# 07_RS485.net
KiCad netlist of a schematic drawn in Altium Designer
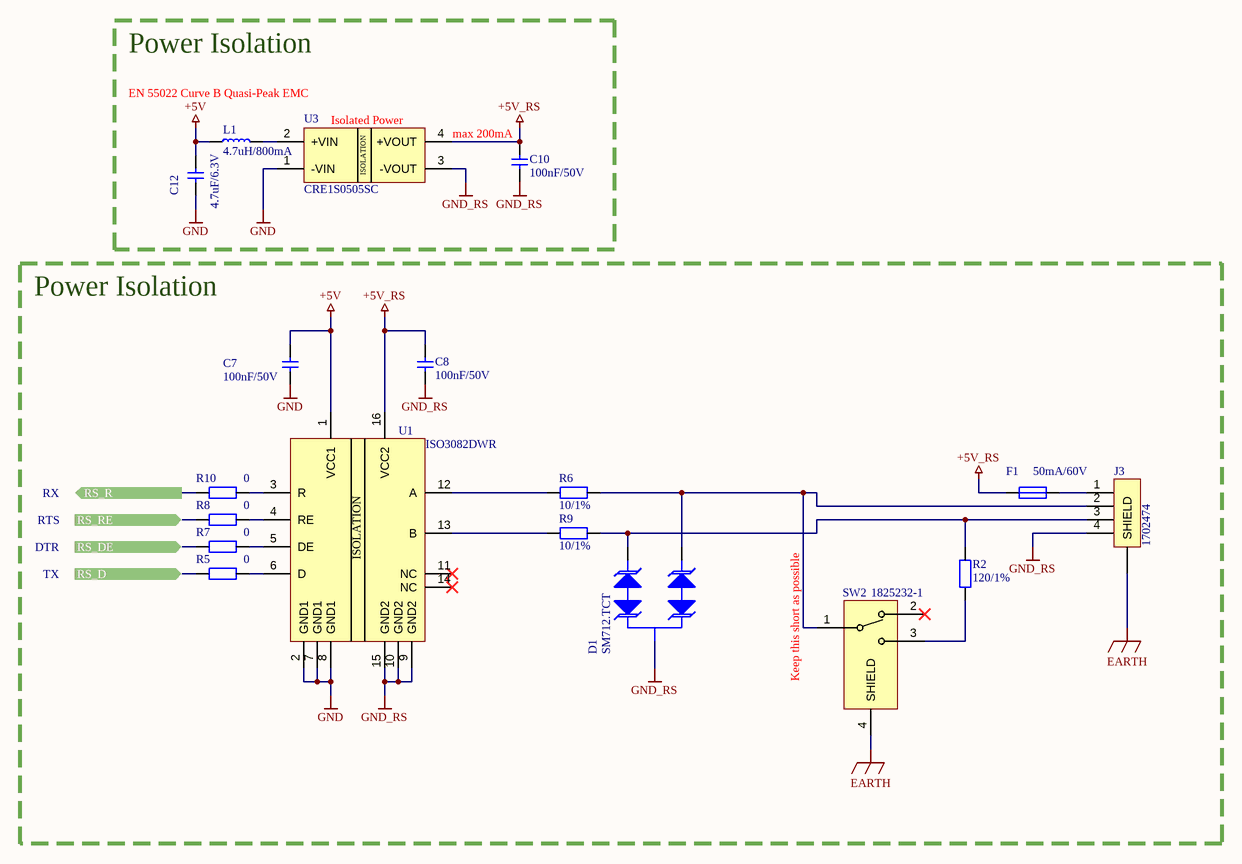
[diagram p0: 07 RS485.SchDoc]

(export (version "E")
  (design (tool "Eeschema 10.0.6"))
  (components
    (comp (ref "C7")
      (value "100nF/50V")
      (footprint "CAPC1005X06N")
      (description "0.1 µF ±10% 50V Ceramic Capacitor X7R 0402 (1005 Metric)")
      (fields
        (field (name "MANUFACTURER") "Murata Electronics")
        (field (name "MFR_PART_NUMBER") "GCM155R71H104KE02J")
      )
      (libsource (lib "altium_symbol") (part "GCM155R71H104KE02J"))
    )
    (comp (ref "C8")
      (value "100nF/50V")
      (footprint "CAPC1005X06N")
      (description "0.1 µF ±10% 50V Ceramic Capacitor X7R 0402 (1005 Metric)")
      (fields
        (field (name "MANUFACTURER") "Murata Electronics")
        (field (name "MFR_PART_NUMBER") "GCM155R71H104KE02J")
      )
      (libsource (lib "altium_symbol") (part "GCM155R71H104KE02J"))
    )
    (comp (ref "C10")
      (value "100nF/50V")
      (footprint "CAPC1005X06N")
      (description "0.1 µF ±10% 50V Ceramic Capacitor X7R 0402 (1005 Metric)")
      (fields
        (field (name "MANUFACTURER") "Murata Electronics")
        (field (name "MFR_PART_NUMBER") "GCM155R71H104KE02J")
      )
      (libsource (lib "altium_symbol") (part "GCM155R71H104KE02J"))
    )
    (comp (ref "C12")
      (value "4.7uF/6.3V")
      (footprint "CAPC1005X06N")
      (description "4.7 µF ±20% 6.3V Ceramic Capacitor X5R 0402 (1005 Metric)")
      (fields (field (name "MANUFACTURER") "Taiyo Yuden") (field (name "MFR_PART_NUMBER") "JMK105BBJ475MVHF"))
      (libsource (lib "altium_symbol") (part "JMK105BBJ475MVHF"))
    )
    (comp (ref "D1")
      (value "SM712.TCT")
      (footprint "SOT95P237X110-3N")
      (description "26V, 12V Clamp 17A (8/20µs) Ipp Tvs Diode Surface Mount SOT-23-3")
      (fields (field (name "MANUFACTURER") "Semtech Corporation"))
      (libsource (lib "altium_symbol") (part "SM712.TCT"))
    )
    (comp (ref "F1")
      (value "50mA/60V")
      (footprint "DIOC1005X04N")
      (description "Polymeric PTC Resettable Fuse 60V 50 mA Ih Surface Mount 1206 (3216 Metric), Concave")
      (fields (field (name "MANUFACTURER") "Bel Fuse Inc.") (field (name "MFR_PART_NUMBER") "0ZCJ0005FF2E"))
      (libsource (lib "altium_symbol") (part "0ZCJ0005FF2E"))
    )
    (comp (ref "J3")
      (value "1702474")
      (footprint "1702474")
      (description "4 Position Wire to Board Terminal Block Horizontal with Board 0.098\" (2.50mm) Surface Mount")
      (fields (field (name "MANUFACTURER") "Phoenix Contact"))
      (libsource (lib "altium_symbol") (part "1702474"))
    )
    (comp (ref "L1")
      (value "4.7uH/800mA")
      (footprint "INDP3225X23N")
      (description "4.7 µH Unshielded Wirewound Inductor 800 mA 190mOhm Max 1210 (3225 Metric)")
      (fields
        (field (name "MANUFACTURER") "Murata Power Solutions Inc.")
        (field (name "MFR_PART_NUMBER") "82472C")
      )
      (libsource (lib "altium_symbol") (part "82472C"))
    )
    (comp (ref "R2")
      (value "120/1%")
      (footprint "RESC1005X04N")
      (description "120 Ohms ±1% 0.1W, 1/10W Chip Resistor 0402 (1005 Metric) Automotive AEC-Q200 Thick Film")
      (fields
        (field (name "MANUFACTURER") "Panasonic Electronic Components")
        (field (name "MFR_PART_NUMBER") "ERJ-2RKF1200X")
      )
      (libsource (lib "altium_symbol") (part "ERJ-2RKF1200X"))
    )
    (comp (ref "R5")
      (value "0")
      (footprint "RESC1005X04N")
      (description "0 Ohms Jumper Chip Resistor 0402 (1005 Metric) Automotive AEC-Q200 Thick Film")
      (fields
        (field (name "MANUFACTURER") "Panasonic Electronic Components")
        (field (name "MFR_PART_NUMBER") "ERJ-2GE0R00X")
      )
      (libsource (lib "altium_symbol") (part "ERJ-2GE0R00X"))
    )
    (comp (ref "R6")
      (value "10/1%")
      (footprint "RESMELF3614N")
      (fields
        (field (name "MANUFACTURER") "Vishay Beyschlag/Draloric/BC Components")
        (field (name "MFR_PART_NUMBER") "SMM02040C1009FB300")
      )
      (libsource (lib "altium_symbol") (part "SMM02040C1009FB300"))
    )
    (comp (ref "R7")
      (value "0")
      (footprint "RESC1005X04N")
      (description "0 Ohms Jumper Chip Resistor 0402 (1005 Metric) Automotive AEC-Q200 Thick Film")
      (fields
        (field (name "MANUFACTURER") "Panasonic Electronic Components")
        (field (name "MFR_PART_NUMBER") "ERJ-2GE0R00X")
      )
      (libsource (lib "altium_symbol") (part "ERJ-2GE0R00X"))
    )
    (comp (ref "R8")
      (value "0")
      (footprint "RESC1005X04N")
      (description "0 Ohms Jumper Chip Resistor 0402 (1005 Metric) Automotive AEC-Q200 Thick Film")
      (fields
        (field (name "MANUFACTURER") "Panasonic Electronic Components")
        (field (name "MFR_PART_NUMBER") "ERJ-2GE0R00X")
      )
      (libsource (lib "altium_symbol") (part "ERJ-2GE0R00X"))
    )
    (comp (ref "R9")
      (value "10/1%")
      (footprint "RESMELF3614N")
      (fields
        (field (name "MANUFACTURER") "Vishay Beyschlag/Draloric/BC Components")
        (field (name "MFR_PART_NUMBER") "SMM02040C1009FB300")
      )
      (libsource (lib "altium_symbol") (part "SMM02040C1009FB300"))
    )
    (comp (ref "R10")
      (value "0")
      (footprint "RESC1005X04N")
      (description "0 Ohms Jumper Chip Resistor 0402 (1005 Metric) Automotive AEC-Q200 Thick Film")
      (fields
        (field (name "MANUFACTURER") "Panasonic Electronic Components")
        (field (name "MFR_PART_NUMBER") "ERJ-2GE0R00X")
      )
      (libsource (lib "altium_symbol") (part "ERJ-2GE0R00X"))
    )
    (comp (ref "SW2")
      (value "1825232-1")
      (footprint "1825232-1")
      (description "Slide Switch SPDT Through Hole, Right Angle")
      (fields (field (name "MANUFACTURER") "C&K") (field (name "MFR_PART_NUMBER") "JS202011JAQN"))
      (libsource (lib "altium_symbol") (part "1825232-1"))
    )
    (comp (ref "U1")
      (value "ISO3082DWR")
      (footprint "SOIC127P1030X265-16N")
      (description "2/2 Transceiver, Isolated Half RS422, RS485 16-SOIC")
      (fields (field (name "MANUFACTURER") "Texas Instruments"))
      (libsource (lib "altium_symbol") (part "ISO3082DWR"))
    )
    (comp (ref "U3")
      (value "CRE1S0505SC")
      (footprint "CRE1S0505SC")
      (description "Isolated Module DC DC Converter 1 Output 5V 200mA 4.5V - 5.5V Input")
      (fields (field (name "MANUFACTURER") "Murata Power Solutions Inc."))
      (libsource (lib "altium_symbol") (part "CRE1S0505SC"))
    )
  )
  (nets
    (net (code "1") (name "+5V") (class "Default")
      (node (ref "C12") (pin "2") (pinfunction "2_2") (pintype "passive"))
      (node (ref "C7") (pin "2") (pinfunction "2_2") (pintype "passive"))
      (node (ref "L1") (pin "1") (pinfunction "1_1") (pintype "passive"))
      (node (ref "U1") (pin "1") (pinfunction "VCC1_1") (pintype "passive"))
    )
    (net (code "2") (name "+5V_RS") (class "Default")
      (node (ref "C10") (pin "2") (pinfunction "2_2") (pintype "passive"))
      (node (ref "C8") (pin "2") (pinfunction "2_2") (pintype "passive"))
      (node (ref "F1") (pin "1") (pinfunction "1_1") (pintype "passive"))
      (node (ref "U1") (pin "16") (pinfunction "VCC2_16") (pintype "passive"))
      (node (ref "U3") (pin "4") (pinfunction "+VOUT_4") (pintype "passive"))
    )
    (net (code "3") (name "/RS_D") (class "Default")
      (node (ref "R5") (pin "1") (pinfunction "1_1") (pintype "passive"))
    )
    (net (code "4") (name "/RS_DE") (class "Default")
      (node (ref "R7") (pin "1") (pinfunction "1_1") (pintype "passive"))
    )
    (net (code "5") (name "/RS_R") (class "Default")
      (node (ref "R10") (pin "1") (pinfunction "1_1") (pintype "passive"))
    )
    (net (code "6") (name "/RS_RE") (class "Default")
      (node (ref "R8") (pin "1") (pinfunction "1_1") (pintype "passive"))
    )
    (net (code "7") (name "EARTH") (class "Default")
      (node (ref "J3") (pin "SHIELD") (pinfunction "SHIELD_SHIELD") (pintype "passive"))
      (node (ref "SW2") (pin "4") (pinfunction "SHIELD_4") (pintype "passive"))
    )
    (net (code "8") (name "GND") (class "Default")
      (node (ref "C12") (pin "1") (pinfunction "1_1") (pintype "passive"))
      (node (ref "C7") (pin "1") (pinfunction "1_1") (pintype "passive"))
      (node (ref "U1") (pin "2") (pinfunction "GND1_2") (pintype "passive"))
      (node (ref "U1") (pin "7") (pinfunction "GND1_7") (pintype "passive"))
      (node (ref "U1") (pin "8") (pinfunction "GND1_8") (pintype "passive"))
      (node (ref "U3") (pin "1") (pinfunction "-VIN_1") (pintype "passive"))
    )
    (net (code "9") (name "GND_RS") (class "Default")
      (node (ref "C10") (pin "1") (pinfunction "1_1") (pintype "passive"))
      (node (ref "C8") (pin "1") (pinfunction "1_1") (pintype "passive"))
      (node (ref "D1") (pin "3") (pintype "passive"))
      (node (ref "J3") (pin "4") (pinfunction "4_4") (pintype "passive"))
      (node (ref "U1") (pin "10") (pinfunction "GND2_10") (pintype "passive"))
      (node (ref "U1") (pin "15") (pinfunction "GND2_15") (pintype "passive"))
      (node (ref "U1") (pin "9") (pinfunction "GND2_9") (pintype "passive"))
      (node (ref "U3") (pin "3") (pinfunction "-VOUT_3") (pintype "passive"))
    )
    (net (code "10") (name "Net-(D1-Pad1)") (class "Default")
      (node (ref "D1") (pin "1") (pintype "passive"))
      (node (ref "J3") (pin "3") (pinfunction "3_3") (pintype "passive"))
      (node (ref "R2") (pin "2") (pinfunction "2_2") (pintype "passive"))
      (node (ref "R9") (pin "2") (pinfunction "2_2") (pintype "passive"))
    )
    (net (code "11") (name "Net-(D1-Pad2)") (class "Default")
      (node (ref "D1") (pin "2") (pintype "passive"))
      (node (ref "J3") (pin "2") (pinfunction "2_2") (pintype "passive"))
      (node (ref "R6") (pin "2") (pinfunction "2_2") (pintype "passive"))
      (node (ref "SW2") (pin "1") (pinfunction "1_1") (pintype "passive"))
    )
    (net (code "12") (name "Net-(F1-Pad2)") (class "Default")
      (node (ref "F1") (pin "2") (pinfunction "2_2") (pintype "passive"))
      (node (ref "J3") (pin "1") (pinfunction "1_1") (pintype "passive"))
    )
    (net (code "13") (name "Net-(R2-Pad1)") (class "Default")
      (node (ref "R2") (pin "1") (pinfunction "1_1") (pintype "passive"))
      (node (ref "SW2") (pin "3") (pinfunction "3_3") (pintype "passive"))
    )
    (net (code "14") (name "Net-(U1-A)") (class "Default")
      (node (ref "R6") (pin "1") (pinfunction "1_1") (pintype "passive"))
      (node (ref "U1") (pin "12") (pinfunction "A_12") (pintype "passive"))
    )
    (net (code "15") (name "Net-(U1-B)") (class "Default")
      (node (ref "R9") (pin "1") (pinfunction "1_1") (pintype "passive"))
      (node (ref "U1") (pin "13") (pinfunction "B_13") (pintype "passive"))
    )
    (net (code "16") (name "Net-(U1-D)") (class "Default")
      (node (ref "R5") (pin "2") (pinfunction "2_2") (pintype "passive"))
      (node (ref "U1") (pin "6") (pinfunction "D_6") (pintype "passive"))
    )
    (net (code "17") (name "Net-(U1-DE)") (class "Default")
      (node (ref "R7") (pin "2") (pinfunction "2_2") (pintype "passive"))
      (node (ref "U1") (pin "5") (pinfunction "DE_5") (pintype "passive"))
    )
    (net (code "18") (name "Net-(U1-R)") (class "Default")
      (node (ref "R10") (pin "2") (pinfunction "2_2") (pintype "passive"))
      (node (ref "U1") (pin "3") (pinfunction "R_3") (pintype "passive"))
    )
    (net (code "19") (name "Net-(U1-RE)") (class "Default")
      (node (ref "R8") (pin "2") (pinfunction "2_2") (pintype "passive"))
      (node (ref "U1") (pin "4") (pinfunction "RE_4") (pintype "passive"))
    )
    (net (code "20") (name "Net-(U3-+VIN)") (class "Default")
      (node (ref "L1") (pin "2") (pinfunction "2_2") (pintype "passive"))
      (node (ref "U3") (pin "2") (pinfunction "+VIN_2") (pintype "passive"))
    )
    (net (code "21") (name "unconnected-(SW2-Pad2)") (class "Default")
      (node (ref "SW2") (pin "2") (pinfunction "2_2") (pintype "passive+no_connect"))
    )
    (net (code "22") (name "unconnected-(U1-NC-Pad11)") (class "Default")
      (node (ref "U1") (pin "11") (pinfunction "NC_11") (pintype "passive+no_connect"))
    )
    (net (code "23") (name "unconnected-(U1-NC-Pad14)") (class "Default")
      (node (ref "U1") (pin "14") (pinfunction "NC_14") (pintype "passive+no_connect"))
    )
  )
)
